# USB.net
KiCad netlist of a schematic drawn in Altium Designer
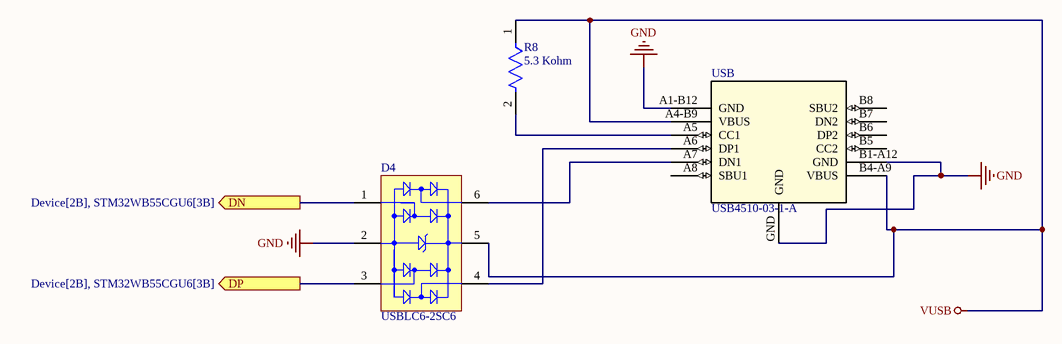
[diagram p0: USB.SchDoc]

(export (version "E")
  (design (tool "Eeschema 10.0.6"))
  (components
    (comp (ref "D4")
      (value "USBLC6-2SC6")
      (footprint "STM-SOT23-6L_V")
      (description "Very low capacitance ESD protection, 3.5 pF, -40 to 125 degC, 6-Pin SOT23, RoHS, Tape and Reel")
      (fields (field (name "MANUFACTURER") "STMicroelectronics"))
      (libsource (lib "Altium Content Vault") (part "STM-USB_DVI_HDMIULC6-4SC6X-SOT23-6L"))
    )
    (comp (ref "R8")
      (value "5.3 Kohm")
      (footprint "FP-RC1005-IPC_C")
      (description "Res Thick Film 0402 1.87kΩ 1% 0.063W ±100ppm/°C Molded SMD T/R")
      (fields (field (name "TOLERANCE") "1%"))
      (libsource (lib "Altium Content Vault") (part "1029c3af85768c4190bb7ad29bc67b5"))
    )
    (comp (ref "USB")
      (value "USB4510-03-1-A")
      (footprint "USB4510-03-1-A")
      (libsource (lib "ReadyButNotListed") (part "USB4510-03-1-A"))
    )
  )
  (nets
    (net (code "1") (name "/DN") (class "Default")
      (node (ref "D4") (pin "1") (pinfunction "I/O_1_1") (pintype "passive"))
    )
    (net (code "2") (name "/DP") (class "Default")
      (node (ref "D4") (pin "3") (pinfunction "I/O_2_3") (pintype "passive"))
    )
    (net (code "3") (name "GND") (class "Default")
      (node (ref "D4") (pin "2") (pinfunction "GND_2") (pintype "passive"))
      (node (ref "USB") (pin "A1-B12") (pinfunction "GND_A1-B12") (pintype "passive"))
      (node (ref "USB") (pin "B1-A12") (pinfunction "GND_B1-A12") (pintype "passive"))
      (node (ref "USB") (pin "GND") (pinfunction "GND_GND") (pintype "passive"))
    )
    (net (code "4") (name "Net-(D4-I{slash}O_3)") (class "Default")
      (node (ref "D4") (pin "4") (pinfunction "I/O_3_4") (pintype "passive"))
      (node (ref "USB") (pin "A6") (pinfunction "DP1_A6") (pintype "bidirectional"))
    )
    (net (code "5") (name "Net-(D4-I{slash}O_4)") (class "Default")
      (node (ref "D4") (pin "6") (pinfunction "I/O_4_6") (pintype "passive"))
      (node (ref "USB") (pin "A7") (pinfunction "DN1_A7") (pintype "bidirectional"))
    )
    (net (code "6") (name "Net-(USB-CC1)") (class "Default")
      (node (ref "R8") (pin "2") (pinfunction "2_2") (pintype "passive"))
      (node (ref "USB") (pin "A5") (pinfunction "CC1_A5") (pintype "bidirectional"))
    )
    (net (code "7") (name "VUSB") (class "Default")
      (node (ref "D4") (pin "5") (pinfunction "VBUS_5") (pintype "passive"))
      (node (ref "R8") (pin "1") (pinfunction "1_1") (pintype "passive"))
      (node (ref "USB") (pin "A4-B9") (pinfunction "VBUS_A4-B9") (pintype "power_in"))
      (node (ref "USB") (pin "B4-A9") (pinfunction "VBUS_B4-A9") (pintype "power_in"))
    )
    (net (code "8") (name "unconnected-(USB-CC2-PadB5)") (class "Default")
      (node (ref "USB") (pin "B5") (pinfunction "CC2_B5") (pintype "bidirectional"))
    )
    (net (code "9") (name "unconnected-(USB-DN2-PadB7)") (class "Default")
      (node (ref "USB") (pin "B7") (pinfunction "DN2_B7") (pintype "bidirectional"))
    )
    (net (code "10") (name "unconnected-(USB-DP2-PadB6)") (class "Default")
      (node (ref "USB") (pin "B6") (pinfunction "DP2_B6") (pintype "bidirectional"))
    )
    (net (code "11") (name "unconnected-(USB-SBU1-PadA8)") (class "Default")
      (node (ref "USB") (pin "A8") (pinfunction "SBU1_A8") (pintype "bidirectional"))
    )
    (net (code "12") (name "unconnected-(USB-SBU2-PadB8)") (class "Default")
      (node (ref "USB") (pin "B8") (pinfunction "SBU2_B8") (pintype "bidirectional"))
    )
  )
)
